# R016_-_Slice_of_Radio_v1_1.net
KiCad netlist of a schematic drawn in EAGLE
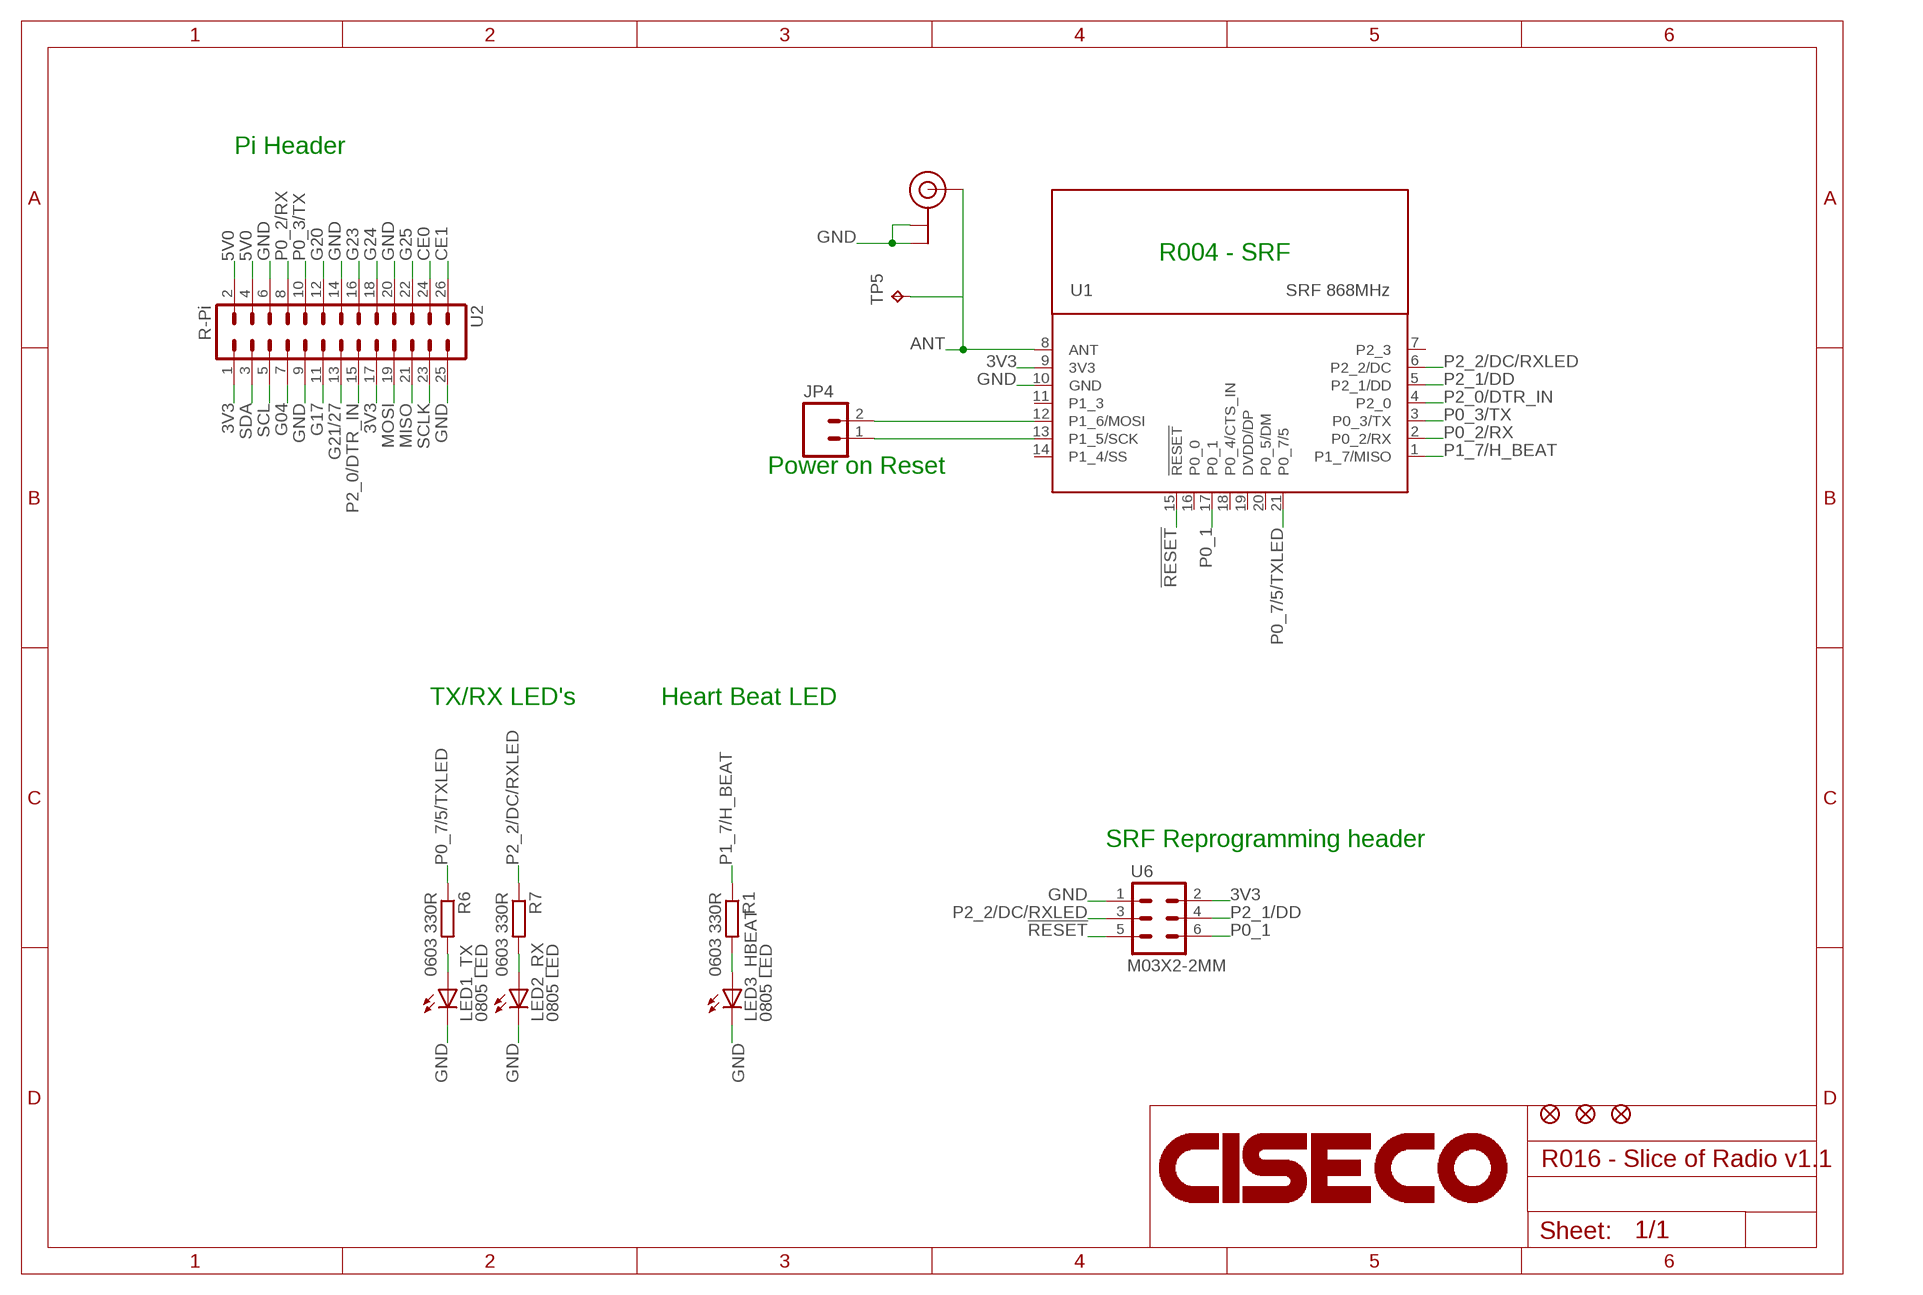
[diagram p0: schematic, sheet 1]

(export (version "E")
  (design (tool "Eeschema 10.0.6"))
  (components
    (comp (ref "JP1")
      (value "FIDUCIAL1X2.5-STOP")
      (footprint "eagle-import:FIDUCIAL-1X2.5-STOP")
      (libsource (lib "eagle-import") (part "FIDUCIAL1X2.5-STOP"))
    )
    (comp (ref "JP2")
      (value "FIDUCIAL1X2.5-STOP")
      (footprint "eagle-import:FIDUCIAL-1X2.5-STOP")
      (libsource (lib "eagle-import") (part "FIDUCIAL1X2.5-STOP"))
    )
    (comp (ref "JP3")
      (value "FIDUCIAL1X2.5-STOP")
      (footprint "eagle-import:FIDUCIAL-1X2.5-STOP")
      (libsource (lib "eagle-import") (part "FIDUCIAL1X2.5-STOP"))
    )
    (comp (ref "JP4")
      (value "M02PTH")
      (footprint "eagle-import:1X02")
      (libsource (lib "eagle-import") (part "M02PTH"))
    )
    (comp (ref "LED1_TX")
      (value "0805 LED")
      (footprint "eagle-import:LED-0805-CORRECT")
      (libsource (lib "eagle-import") (part "LED0805-CORRECT"))
    )
    (comp (ref "LED2_RX")
      (value "0805 LED")
      (footprint "eagle-import:LED-0805-CORRECT")
      (libsource (lib "eagle-import") (part "LED0805-CORRECT"))
    )
    (comp (ref "LED3_HBEAT")
      (value "0805 LED")
      (footprint "eagle-import:LED-0805-CORRECT")
      (libsource (lib "eagle-import") (part "LED0805-CORRECT"))
    )
    (comp (ref "LOGO1")
      (value "CISECOLOGO-2MM")
      (footprint "eagle-import:CISECO-2MM")
      (libsource (lib "eagle-import") (part "CISECOLOGO-2MM"))
    )
    (comp (ref "R1")
      (value "0603 330R")
      (footprint "eagle-import:C0603K-SMALL")
      (libsource (lib "eagle-import") (part "R-EU_0603K-SMALL"))
    )
    (comp (ref "R6")
      (value "0603 330R")
      (footprint "eagle-import:C0603K-SMALL")
      (libsource (lib "eagle-import") (part "R-EU_0603K-SMALL"))
    )
    (comp (ref "R7")
      (value "0603 330R")
      (footprint "eagle-import:C0603K-SMALL")
      (libsource (lib "eagle-import") (part "R-EU_0603K-SMALL"))
    )
    (comp (ref "TP5")
      (value "TPPAD1-13")
      (footprint "eagle-import:P1-13")
      (libsource (lib "eagle-import") (part "TPPAD1-13"))
    )
    (comp (ref "U1")
      (value "SRF 868MHz")
      (footprint "eagle-import:SRF-LANDING-1.2")
      (libsource (lib "eagle-import") (part "SRF-LANDING-1.2"))
    )
    (comp (ref "U2")
      (value "R-Pi")
      (footprint "eagle-import:EVE-BOARD-REF-LOCK")
      (libsource (lib "eagle-import") (part "EVE-REFRENCE-LOCK"))
    )
    (comp (ref "U6")
      (value "M03X2-2MM")
      (footprint "eagle-import:2X3_2MM")
      (libsource (lib "eagle-import") (part "M03X2-2MM"))
    )
    (comp (ref "U11")
      (value "U.FL 868")
      (footprint "eagle-import:U.FL")
      (libsource (lib "eagle-import") (part "U.FL"))
    )
  )
  (nets
    (net (code "1") (name "/3V3") (class "Default")
      (node (ref "U1") (pin "9") (pinfunction "3V3_9") (pintype "power_in"))
      (node (ref "U2") (pin "1") (pinfunction "1_1") (pintype "passive"))
      (node (ref "U2") (pin "17") (pinfunction "17_17") (pintype "passive"))
      (node (ref "U6") (pin "2") (pinfunction "2_2") (pintype "passive"))
    )
    (net (code "2") (name "/5V0") (class "Default")
      (node (ref "U2") (pin "2") (pinfunction "2_2") (pintype "passive"))
      (node (ref "U2") (pin "4") (pinfunction "4_4") (pintype "passive"))
    )
    (net (code "3") (name "/ANT") (class "Default")
      (node (ref "TP5") (pin "TP") (pinfunction "TP_TP") (pintype "input"))
      (node (ref "U1") (pin "8") (pinfunction "ANT_8") (pintype "output"))
      (node (ref "U11") (pin "P$3") (pinfunction "SIGNAL_P$3") (pintype "bidirectional"))
    )
    (net (code "4") (name "/CE0") (class "Default")
      (node (ref "U2") (pin "24") (pinfunction "24_24") (pintype "passive"))
    )
    (net (code "5") (name "/CE1") (class "Default")
      (node (ref "U2") (pin "26") (pinfunction "26_26") (pintype "passive"))
    )
    (net (code "6") (name "/G04") (class "Default")
      (node (ref "U2") (pin "7") (pinfunction "7_7") (pintype "passive"))
    )
    (net (code "7") (name "/G17") (class "Default")
      (node (ref "U2") (pin "11") (pinfunction "11_11") (pintype "passive"))
    )
    (net (code "8") (name "/G20") (class "Default")
      (node (ref "U2") (pin "12") (pinfunction "12_12") (pintype "passive"))
    )
    (net (code "9") (name "/G21{slash}27") (class "Default")
      (node (ref "U2") (pin "13") (pinfunction "13_13") (pintype "passive"))
    )
    (net (code "10") (name "/G23") (class "Default")
      (node (ref "U2") (pin "16") (pinfunction "16_16") (pintype "passive"))
    )
    (net (code "11") (name "/G24") (class "Default")
      (node (ref "U2") (pin "18") (pinfunction "18_18") (pintype "passive"))
    )
    (net (code "12") (name "/G25") (class "Default")
      (node (ref "U2") (pin "22") (pinfunction "22_22") (pintype "passive"))
    )
    (net (code "13") (name "/GND") (class "Default")
      (node (ref "LED1_TX") (pin "C") (pinfunction "C_C") (pintype "passive"))
      (node (ref "LED2_RX") (pin "C") (pinfunction "C_C") (pintype "passive"))
      (node (ref "LED3_HBEAT") (pin "C") (pinfunction "C_C") (pintype "passive"))
      (node (ref "U1") (pin "10") (pinfunction "GND_10") (pintype "power_in"))
      (node (ref "U11") (pin "P$1") (pinfunction "GND_P$1") (pintype "bidirectional"))
      (node (ref "U11") (pin "P$2") (pinfunction "GND_P$2") (pintype "bidirectional"))
      (node (ref "U2") (pin "14") (pinfunction "14_14") (pintype "passive"))
      (node (ref "U2") (pin "20") (pinfunction "20_20") (pintype "passive"))
      (node (ref "U2") (pin "25") (pinfunction "25_25") (pintype "passive"))
      (node (ref "U2") (pin "6") (pinfunction "6_6") (pintype "passive"))
      (node (ref "U2") (pin "9") (pinfunction "9_9") (pintype "passive"))
      (node (ref "U6") (pin "1") (pinfunction "1_1") (pintype "passive"))
    )
    (net (code "14") (name "/MISO") (class "Default")
      (node (ref "U2") (pin "21") (pinfunction "21_21") (pintype "passive"))
    )
    (net (code "15") (name "/MOSI") (class "Default")
      (node (ref "U2") (pin "19") (pinfunction "19_19") (pintype "passive"))
    )
    (net (code "16") (name "/P0_1") (class "Default")
      (node (ref "U1") (pin "17") (pinfunction "P0_1_17") (pintype "bidirectional"))
      (node (ref "U6") (pin "6") (pinfunction "6_6") (pintype "passive"))
    )
    (net (code "17") (name "/P0_2{slash}RX") (class "Default")
      (node (ref "U1") (pin "2") (pinfunction "P0_2/RX_2") (pintype "bidirectional"))
      (node (ref "U2") (pin "8") (pinfunction "8_8") (pintype "passive"))
    )
    (net (code "18") (name "/P0_3{slash}TX") (class "Default")
      (node (ref "U1") (pin "3") (pinfunction "P0_3/TX_3") (pintype "bidirectional"))
      (node (ref "U2") (pin "10") (pinfunction "10_10") (pintype "passive"))
    )
    (net (code "19") (name "/P0_7{slash}5{slash}TXLED") (class "Default")
      (node (ref "R6") (pin "1") (pinfunction "1_1") (pintype "passive"))
      (node (ref "U1") (pin "21") (pinfunction "P0_7/5_21") (pintype "bidirectional"))
    )
    (net (code "20") (name "/P1_7{slash}H_BEAT") (class "Default")
      (node (ref "R1") (pin "1") (pinfunction "1_1") (pintype "passive"))
      (node (ref "U1") (pin "1") (pinfunction "P1_7/MISO_1") (pintype "bidirectional"))
    )
    (net (code "21") (name "/P2_0{slash}DTR_IN") (class "Default")
      (node (ref "U1") (pin "4") (pinfunction "P2_0_4") (pintype "bidirectional"))
      (node (ref "U2") (pin "15") (pinfunction "15_15") (pintype "passive"))
    )
    (net (code "22") (name "/P2_1{slash}DD") (class "Default")
      (node (ref "U1") (pin "5") (pinfunction "P2_1/DD_5") (pintype "bidirectional"))
      (node (ref "U6") (pin "4") (pinfunction "4_4") (pintype "passive"))
    )
    (net (code "23") (name "/P2_2{slash}DC{slash}RXLED") (class "Default")
      (node (ref "R7") (pin "1") (pinfunction "1_1") (pintype "passive"))
      (node (ref "U1") (pin "6") (pinfunction "P2_2/DC_6") (pintype "bidirectional"))
      (node (ref "U6") (pin "3") (pinfunction "3_3") (pintype "passive"))
    )
    (net (code "24") (name "/SCL") (class "Default")
      (node (ref "U2") (pin "5") (pinfunction "5_5") (pintype "passive"))
    )
    (net (code "25") (name "/SCLK") (class "Default")
      (node (ref "U2") (pin "23") (pinfunction "23_23") (pintype "passive"))
    )
    (net (code "26") (name "/SDA") (class "Default")
      (node (ref "U2") (pin "3") (pinfunction "3_3") (pintype "passive"))
    )
    (net (code "27") (name "/~{RESET}") (class "Default")
      (node (ref "U1") (pin "15") (pinfunction "~{RESET}_15") (pintype "input"))
      (node (ref "U6") (pin "5") (pinfunction "5_5") (pintype "passive"))
    )
    (net (code "28") (name "Net-(LED1_TX-PadA)") (class "Default")
      (node (ref "LED1_TX") (pin "A") (pinfunction "A_A") (pintype "passive"))
      (node (ref "R6") (pin "2") (pinfunction "2_2") (pintype "passive"))
    )
    (net (code "29") (name "Net-(LED2_RX-PadA)") (class "Default")
      (node (ref "LED2_RX") (pin "A") (pinfunction "A_A") (pintype "passive"))
      (node (ref "R7") (pin "2") (pinfunction "2_2") (pintype "passive"))
    )
    (net (code "30") (name "Net-(LED3_HBEAT-PadA)") (class "Default")
      (node (ref "LED3_HBEAT") (pin "A") (pinfunction "A_A") (pintype "passive"))
      (node (ref "R1") (pin "2") (pinfunction "2_2") (pintype "passive"))
    )
    (net (code "31") (name "Net-(U1-P1_5{slash}SCK)") (class "Default")
      (node (ref "JP4") (pin "1") (pinfunction "1_1") (pintype "passive"))
      (node (ref "U1") (pin "13") (pinfunction "P1_5/SCK_13") (pintype "bidirectional"))
    )
    (net (code "32") (name "Net-(U1-P1_6{slash}MOSI)") (class "Default")
      (node (ref "JP4") (pin "2") (pinfunction "2_2") (pintype "passive"))
      (node (ref "U1") (pin "12") (pinfunction "P1_6/MOSI_12") (pintype "bidirectional"))
    )
    (net (code "33") (name "unconnected-(U1-DVDD{slash}DP-Pad19)") (class "Default")
      (node (ref "U1") (pin "19") (pinfunction "DVDD/DP_19") (pintype "bidirectional"))
    )
    (net (code "34") (name "unconnected-(U1-P0_0-Pad16)") (class "Default")
      (node (ref "U1") (pin "16") (pinfunction "P0_0_16") (pintype "bidirectional"))
    )
    (net (code "35") (name "unconnected-(U1-P0_4{slash}CTS_IN-Pad18)") (class "Default")
      (node (ref "U1") (pin "18") (pinfunction "P0_4/CTS_IN_18") (pintype "bidirectional"))
    )
    (net (code "36") (name "unconnected-(U1-P0_5{slash}DM-Pad20)") (class "Default")
      (node (ref "U1") (pin "20") (pinfunction "P0_5/DM_20") (pintype "bidirectional"))
    )
    (net (code "37") (name "unconnected-(U1-P1_3-Pad11)") (class "Default")
      (node (ref "U1") (pin "11") (pinfunction "P1_3_11") (pintype "bidirectional"))
    )
    (net (code "38") (name "unconnected-(U1-P1_4{slash}SS-Pad14)") (class "Default")
      (node (ref "U1") (pin "14") (pinfunction "P1_4/SS_14") (pintype "bidirectional"))
    )
    (net (code "39") (name "unconnected-(U1-P2_3-Pad7)") (class "Default")
      (node (ref "U1") (pin "7") (pinfunction "P2_3_7") (pintype "bidirectional"))
    )
  )
)
